# power_supply_and_battery_management.net
KiCad netlist of a schematic drawn in Altium Designer
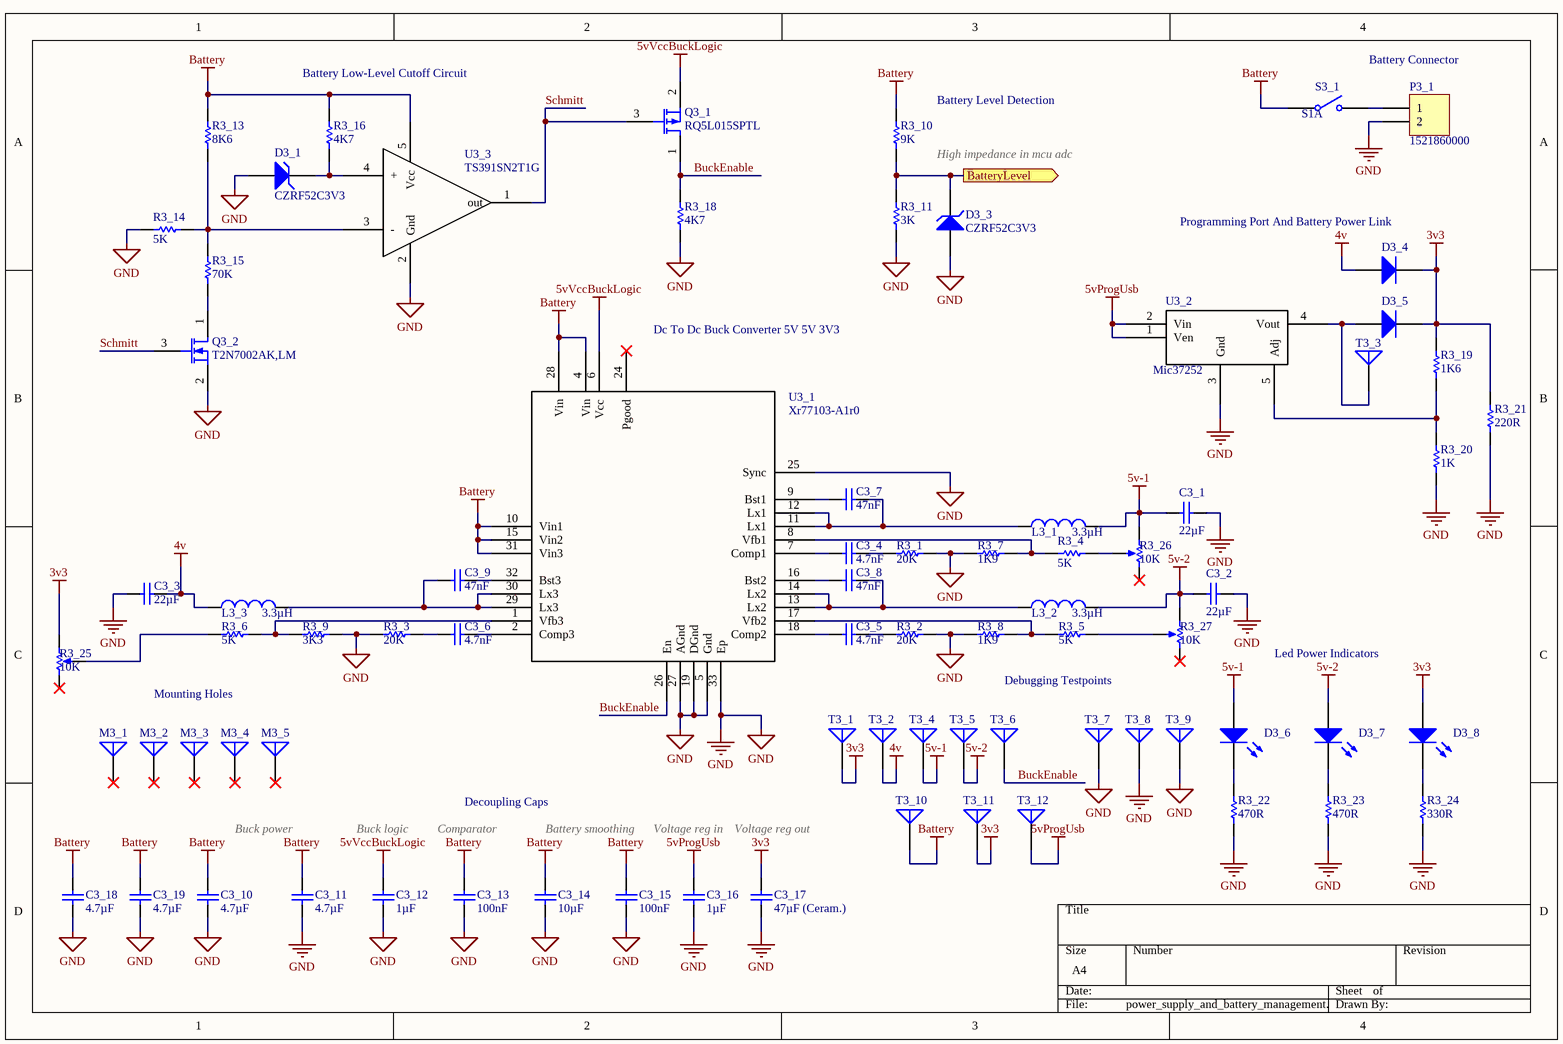
[diagram p0: power_supply_and_battery_management.schdoc]

(export (version "E")
  (design (tool "Eeschema 10.0.6"))
  (components
    (comp (ref "C3_1")
      (value "22µF")
      (footprint "C1206")
      (description "Capacitor")
      (fields (field (name "Comment") "CL31A226KOHNNNE") (field (name "PUBLISHER") "Altium Limited"))
      (libsource (lib "Miscellaneous Devices") (part "Cap"))
    )
    (comp (ref "C3_2")
      (value "22µF")
      (footprint "C1206")
      (description "Capacitor")
      (fields (field (name "Comment") "CL31A226KOHNNNE") (field (name "PUBLISHER") "Altium Limited"))
      (libsource (lib "Miscellaneous Devices") (part "Cap"))
    )
    (comp (ref "C3_3")
      (value "22µF")
      (footprint "C1206")
      (description "Capacitor")
      (fields (field (name "Comment") "CL31A226KOHNNNE") (field (name "PUBLISHER") "Altium Limited"))
      (libsource (lib "Miscellaneous Devices") (part "Cap"))
    )
    (comp (ref "C3_4")
      (value "4.7nF")
      (footprint "C1206")
      (description "Capacitor")
      (fields (field (name "Comment") "CML1206X7R472KT50V") (field (name "PUBLISHER") "Altium Limited"))
      (libsource (lib "Miscellaneous Devices") (part "Cap"))
    )
    (comp (ref "C3_5")
      (value "4.7nF")
      (footprint "C1206")
      (description "Capacitor")
      (fields (field (name "Comment") "CML1206X7R472KT50V") (field (name "PUBLISHER") "Altium Limited"))
      (libsource (lib "Miscellaneous Devices") (part "Cap"))
    )
    (comp (ref "C3_6")
      (value "4.7nF")
      (footprint "C1206")
      (description "Capacitor")
      (fields (field (name "Comment") "CML1206X7R472KT50V") (field (name "PUBLISHER") "Altium Limited"))
      (libsource (lib "Miscellaneous Devices") (part "Cap"))
    )
    (comp (ref "C3_7")
      (value "47nF")
      (footprint "C1206")
      (description "Capacitor")
      (fields (field (name "Comment") "885012208085") (field (name "PUBLISHER") "Altium Limited"))
      (libsource (lib "Miscellaneous Devices") (part "Cap"))
    )
    (comp (ref "C3_8")
      (value "47nF")
      (footprint "C1206")
      (description "Capacitor")
      (fields (field (name "Comment") "885012208085") (field (name "PUBLISHER") "Altium Limited"))
      (libsource (lib "Miscellaneous Devices") (part "Cap"))
    )
    (comp (ref "C3_9")
      (value "47nF")
      (footprint "C1206")
      (description "Capacitor")
      (fields (field (name "Comment") "885012208085") (field (name "PUBLISHER") "Altium Limited"))
      (libsource (lib "Miscellaneous Devices") (part "Cap"))
    )
    (comp (ref "C3_10")
      (value "4.7µF")
      (footprint "C1206")
      (description "Capacitor")
      (fields (field (name "Comment") "CM316X5R475K25AT") (field (name "PUBLISHER") "Altium Limited"))
      (libsource (lib "Miscellaneous Devices") (part "Cap"))
    )
    (comp (ref "C3_11")
      (value "4.7µF")
      (footprint "C1206")
      (description "Capacitor")
      (fields (field (name "Comment") "CM316X5R475K25AT") (field (name "PUBLISHER") "Altium Limited"))
      (libsource (lib "Miscellaneous Devices") (part "Cap"))
    )
    (comp (ref "C3_12")
      (value "1µF")
      (footprint "C1206")
      (description "Capacitor")
      (fields (field (name "Comment") "885382208005") (field (name "PUBLISHER") "Altium Limited"))
      (libsource (lib "Miscellaneous Devices") (part "Cap"))
    )
    (comp (ref "C3_13")
      (value "100nF")
      (footprint "C1206")
      (description "Capacitor")
      (fields (field (name "Comment") "12063C104MAT2A") (field (name "PUBLISHER") "Altium Limited"))
      (libsource (lib "Miscellaneous Devices") (part "Cap"))
    )
    (comp (ref "C3_14")
      (value "10µF")
      (footprint "C1206")
      (description "Capacitor")
      (fields (field (name "Comment") "EMK316BJ106MLHT") (field (name "PUBLISHER") "Altium Limited"))
      (libsource (lib "Miscellaneous Devices") (part "Cap"))
    )
    (comp (ref "C3_15")
      (value "100nF")
      (footprint "C1206")
      (description "Capacitor")
      (fields (field (name "Comment") "12063C104MAT2A") (field (name "PUBLISHER") "Altium Limited"))
      (libsource (lib "Miscellaneous Devices") (part "Cap"))
    )
    (comp (ref "C3_16")
      (value "1µF")
      (footprint "C1206")
      (description "Capacitor")
      (fields (field (name "Comment") "885382208005") (field (name "PUBLISHER") "Altium Limited"))
      (libsource (lib "Miscellaneous Devices") (part "Cap"))
    )
    (comp (ref "C3_17")
      (value "47µF (Ceram.)")
      (footprint "C1206")
      (description "Capacitor")
      (fields (field (name "Comment") "EMK316BBJ476ML-T") (field (name "PUBLISHER") "Altium Limited"))
      (libsource (lib "Miscellaneous Devices") (part "Cap"))
    )
    (comp (ref "C3_18")
      (value "4.7µF")
      (footprint "C1206")
      (description "Capacitor")
      (fields (field (name "Comment") "CM316X5R475K25AT") (field (name "PUBLISHER") "Altium Limited"))
      (libsource (lib "Miscellaneous Devices") (part "Cap"))
    )
    (comp (ref "C3_19")
      (value "4.7µF")
      (footprint "C1206")
      (description "Capacitor")
      (fields (field (name "Comment") "CM316X5R475K25AT") (field (name "PUBLISHER") "Altium Limited"))
      (libsource (lib "Miscellaneous Devices") (part "Cap"))
    )
    (comp (ref "D3_1")
      (value "CZRF52C3V3")
      (footprint "C1206-POLARIZED")
      (description "Zener Diode")
      (fields (field (name "PUBLISHER") "Altium Limited"))
      (libsource (lib "Miscellaneous Devices") (part "D Zener"))
    )
    (comp (ref "D3_3")
      (value "CZRF52C3V3")
      (footprint "C1206-POLARIZED")
      (description "Zener Diode")
      (fields (field (name "PUBLISHER") "Altium Limited"))
      (libsource (lib "Miscellaneous Devices") (part "D Zener"))
    )
    (comp (ref "D3_4")
      (value "ACDBN160-HF")
      (footprint "C1206-POLARIZED")
      (description "Default Diode")
      (fields (field (name "PUBLISHER") "Altium Limited"))
      (libsource (lib "Miscellaneous Devices") (part "Diode"))
    )
    (comp (ref "D3_5")
      (value "ACDBN160-HF")
      (footprint "C1206-POLARIZED")
      (description "Default Diode")
      (fields (field (name "PUBLISHER") "Altium Limited"))
      (libsource (lib "Miscellaneous Devices") (part "Diode"))
    )
    (comp (ref "D3_6")
      (value "APT3216SGC")
      (footprint "C1206-POLARIZED")
      (description "Typical INFRARED GaAs LED")
      (fields (field (name "PUBLISHER") "Altium Limited"))
      (libsource (lib "Miscellaneous Devices") (part "LED0"))
    )
    (comp (ref "D3_7")
      (value "APT3216SGC")
      (footprint "C1206-POLARIZED")
      (description "Typical INFRARED GaAs LED")
      (fields (field (name "PUBLISHER") "Altium Limited"))
      (libsource (lib "Miscellaneous Devices") (part "LED0"))
    )
    (comp (ref "D3_8")
      (value "APT3216SGC")
      (footprint "C1206-POLARIZED")
      (description "Typical INFRARED GaAs LED")
      (fields (field (name "PUBLISHER") "Altium Limited"))
      (libsource (lib "Miscellaneous Devices") (part "LED0"))
    )
    (comp (ref "L3_1")
      (value "3.3µH")
      (footprint "mpxv1D0830")
      (description "Inductor")
      (fields (field (name "Comment") "MPXV1D0830L3R3") (field (name "PUBLISHER") "Altium Limited"))
      (libsource (lib "Miscellaneous Devices") (part "Inductor"))
    )
    (comp (ref "L3_2")
      (value "3.3µH")
      (footprint "mpxv1D0830")
      (description "Inductor")
      (fields (field (name "Comment") "MPXV1D0830L3R3") (field (name "PUBLISHER") "Altium Limited"))
      (libsource (lib "Miscellaneous Devices") (part "Inductor"))
    )
    (comp (ref "L3_3")
      (value "3.3µH")
      (footprint "mpxv1D0830")
      (description "Inductor")
      (fields (field (name "Comment") "MPXV1D0830L3R3") (field (name "PUBLISHER") "Altium Limited"))
      (libsource (lib "Miscellaneous Devices") (part "Inductor"))
    )
    (comp (ref "M3_1")
      (value "Mounting Hole")
      (footprint "MOUNTING-HOLE-M3")
      (description "Generic Antenna")
      (fields (field (name "PUBLISHER") "Altium Limited"))
      (libsource (lib "Miscellaneous Devices") (part "Antenna"))
    )
    (comp (ref "M3_2")
      (value "Mounting Hole")
      (footprint "MOUNTING-HOLE-M3")
      (description "Generic Antenna")
      (fields (field (name "PUBLISHER") "Altium Limited"))
      (libsource (lib "Miscellaneous Devices") (part "Antenna"))
    )
    (comp (ref "M3_3")
      (value "Mounting Hole")
      (footprint "MOUNTING-HOLE-M3")
      (description "Generic Antenna")
      (fields (field (name "PUBLISHER") "Altium Limited"))
      (libsource (lib "Miscellaneous Devices") (part "Antenna"))
    )
    (comp (ref "M3_4")
      (value "Mounting Hole")
      (footprint "MOUNTING-HOLE-M3")
      (description "Generic Antenna")
      (fields (field (name "PUBLISHER") "Altium Limited"))
      (libsource (lib "Miscellaneous Devices") (part "Antenna"))
    )
    (comp (ref "M3_5")
      (value "Mounting Hole")
      (footprint "MOUNTING-HOLE-M3")
      (description "Generic Antenna")
      (fields (field (name "PUBLISHER") "Altium Limited"))
      (libsource (lib "Miscellaneous Devices") (part "Antenna"))
    )
    (comp (ref "P3_1")
      (value "1521860000")
      (footprint "HDR1X2-508-POLARIZED")
      (description "Header, 2-Pin")
      (fields (field (name "PUBLISHER") "Altium Limited"))
      (libsource (lib "Miscellaneous Connectors") (part "Header 2"))
    )
    (comp (ref "Q3_1")
      (value "RQ5L015SPTL")
      (footprint "SOT23_L")
      (description "P-Channel MOSFET")
      (fields (field (name "PUBLISHER") "Altium Limited"))
      (libsource (lib "Miscellaneous Devices") (part "MOSFET-P"))
    )
    (comp (ref "Q3_2")
      (value "T2N7002AK,LM")
      (footprint "SOT23_L")
      (description "N-Channel MOSFET")
      (fields (field (name "PUBLISHER") "Altium Limited"))
      (libsource (lib "Miscellaneous Devices") (part "MOSFET-N"))
    )
    (comp (ref "R3_1")
      (value "20K")
      (footprint "C1206")
      (description "Resistor")
      (fields (field (name "Comment") "Res1") (field (name "PUBLISHER") "Altium Limited"))
      (libsource (lib "Miscellaneous Devices") (part "Res1"))
    )
    (comp (ref "R3_2")
      (value "20K")
      (footprint "C1206")
      (description "Resistor")
      (fields (field (name "Comment") "Res1") (field (name "PUBLISHER") "Altium Limited"))
      (libsource (lib "Miscellaneous Devices") (part "Res1"))
    )
    (comp (ref "R3_3")
      (value "20K")
      (footprint "C1206")
      (description "Resistor")
      (fields (field (name "Comment") "Res1") (field (name "PUBLISHER") "Altium Limited"))
      (libsource (lib "Miscellaneous Devices") (part "Res1"))
    )
    (comp (ref "R3_4")
      (value "5K")
      (footprint "C1206")
      (description "Resistor")
      (fields (field (name "Comment") "Res1") (field (name "PUBLISHER") "Altium Limited"))
      (libsource (lib "Miscellaneous Devices") (part "Res1"))
    )
    (comp (ref "R3_5")
      (value "5K")
      (footprint "C1206")
      (description "Resistor")
      (fields (field (name "Comment") "Res1") (field (name "PUBLISHER") "Altium Limited"))
      (libsource (lib "Miscellaneous Devices") (part "Res1"))
    )
    (comp (ref "R3_6")
      (value "5K")
      (footprint "C1206")
      (description "Resistor")
      (fields (field (name "Comment") "Res1") (field (name "PUBLISHER") "Altium Limited"))
      (libsource (lib "Miscellaneous Devices") (part "Res1"))
    )
    (comp (ref "R3_7")
      (value "1K9")
      (footprint "C1206")
      (description "Resistor")
      (fields (field (name "Comment") "Res1") (field (name "PUBLISHER") "Altium Limited"))
      (libsource (lib "Miscellaneous Devices") (part "Res1"))
    )
    (comp (ref "R3_8")
      (value "1K9")
      (footprint "C1206")
      (description "Resistor")
      (fields (field (name "Comment") "Res1") (field (name "PUBLISHER") "Altium Limited"))
      (libsource (lib "Miscellaneous Devices") (part "Res1"))
    )
    (comp (ref "R3_9")
      (value "3K3")
      (footprint "C1206")
      (description "Resistor")
      (fields (field (name "Comment") "Res1") (field (name "PUBLISHER") "Altium Limited"))
      (libsource (lib "Miscellaneous Devices") (part "Res1"))
    )
    (comp (ref "R3_10")
      (value "9K")
      (footprint "C1206")
      (description "Resistor")
      (fields (field (name "Comment") "Res1") (field (name "PUBLISHER") "Altium Limited"))
      (libsource (lib "Miscellaneous Devices") (part "Res1"))
    )
    (comp (ref "R3_11")
      (value "3K")
      (footprint "C1206")
      (description "Resistor")
      (fields (field (name "Comment") "Res1") (field (name "PUBLISHER") "Altium Limited"))
      (libsource (lib "Miscellaneous Devices") (part "Res1"))
    )
    (comp (ref "R3_13")
      (value "8K6")
      (footprint "C1206")
      (description "Resistor")
      (fields (field (name "Comment") "Res1") (field (name "PUBLISHER") "Altium Limited"))
      (libsource (lib "Miscellaneous Devices") (part "Res1"))
    )
    (comp (ref "R3_14")
      (value "5K")
      (footprint "C1206")
      (description "Resistor")
      (fields (field (name "Comment") "Res1") (field (name "PUBLISHER") "Altium Limited"))
      (libsource (lib "Miscellaneous Devices") (part "Res1"))
    )
    (comp (ref "R3_15")
      (value "70K")
      (footprint "C1206")
      (description "Resistor")
      (fields (field (name "Comment") "Res1") (field (name "PUBLISHER") "Altium Limited"))
      (libsource (lib "Miscellaneous Devices") (part "Res1"))
    )
    (comp (ref "R3_16")
      (value "4K7")
      (footprint "C1206")
      (description "Resistor")
      (fields (field (name "Comment") "Res1") (field (name "PUBLISHER") "Altium Limited"))
      (libsource (lib "Miscellaneous Devices") (part "Res1"))
    )
    (comp (ref "R3_18")
      (value "4K7")
      (footprint "C1206")
      (description "Resistor")
      (fields (field (name "Comment") "Res1") (field (name "PUBLISHER") "Altium Limited"))
      (libsource (lib "Miscellaneous Devices") (part "Res1"))
    )
    (comp (ref "R3_19")
      (value "1K6")
      (footprint "C1206")
      (description "Resistor")
      (fields (field (name "Comment") "Res1") (field (name "PUBLISHER") "Altium Limited"))
      (libsource (lib "Miscellaneous Devices") (part "Res1"))
    )
    (comp (ref "R3_20")
      (value "1K")
      (footprint "C1206")
      (description "Resistor")
      (fields (field (name "Comment") "Res1") (field (name "PUBLISHER") "Altium Limited"))
      (libsource (lib "Miscellaneous Devices") (part "Res1"))
    )
    (comp (ref "R3_21")
      (value "220R")
      (footprint "C1206")
      (description "Resistor")
      (fields (field (name "Comment") "Res1") (field (name "PUBLISHER") "Altium Limited"))
      (libsource (lib "Miscellaneous Devices") (part "Res1"))
    )
    (comp (ref "R3_22")
      (value "470R")
      (footprint "C1206")
      (description "Resistor")
      (fields (field (name "Comment") "Res1") (field (name "PUBLISHER") "Altium Limited"))
      (libsource (lib "Miscellaneous Devices") (part "Res1"))
    )
    (comp (ref "R3_23")
      (value "470R")
      (footprint "C1206")
      (description "Resistor")
      (fields (field (name "Comment") "Res1") (field (name "PUBLISHER") "Altium Limited"))
      (libsource (lib "Miscellaneous Devices") (part "Res1"))
    )
    (comp (ref "R3_24")
      (value "330R")
      (footprint "C1206")
      (description "Resistor")
      (fields (field (name "Comment") "Res1") (field (name "PUBLISHER") "Altium Limited"))
      (libsource (lib "Miscellaneous Devices") (part "Res1"))
    )
    (comp (ref "R3_25")
      (value "10K")
      (footprint "ST-4ETA103")
      (description "Potentiometer")
      (fields (field (name "Comment") "ST4ETA103") (field (name "PUBLISHER") "Altium Limited"))
      (libsource (lib "") (part "RPot_1"))
    )
    (comp (ref "R3_26")
      (value "10K")
      (footprint "ST-4ETA103")
      (description "Potentiometer")
      (fields (field (name "Comment") "ST4ETA103") (field (name "PUBLISHER") "Altium Limited"))
      (libsource (lib "Miscellaneous Devices") (part "RPot"))
    )
    (comp (ref "R3_27")
      (value "10K")
      (footprint "ST-4ETA103")
      (description "Potentiometer")
      (fields (field (name "Comment") "ST4ETA103") (field (name "PUBLISHER") "Altium Limited"))
      (libsource (lib "Miscellaneous Devices") (part "RPot"))
    )
    (comp (ref "S3_1")
      (value "S1A")
      (footprint "SW2-THR")
      (description "Single-Pole, Single-Throw Switch")
      (fields (field (name "PUBLISHER") "Altium Limited"))
      (libsource (lib "Miscellaneous Devices") (part "SW-SPST"))
    )
    (comp (ref "T3_1")
      (value "Mounting Hole")
      (footprint "TESTPOINT")
      (description "Generic Antenna")
      (fields (field (name "PUBLISHER") "Altium Limited"))
      (libsource (lib "Miscellaneous Devices") (part "Antenna"))
    )
    (comp (ref "T3_2")
      (value "Mounting Hole")
      (footprint "TESTPOINT")
      (description "Generic Antenna")
      (fields (field (name "PUBLISHER") "Altium Limited"))
      (libsource (lib "Miscellaneous Devices") (part "Antenna"))
    )
    (comp (ref "T3_3")
      (value "Mounting Hole")
      (footprint "TESTPOINT")
      (description "Generic Antenna")
      (fields (field (name "PUBLISHER") "Altium Limited"))
      (libsource (lib "Miscellaneous Devices") (part "Antenna"))
    )
    (comp (ref "T3_4")
      (value "Mounting Hole")
      (footprint "TESTPOINT")
      (description "Generic Antenna")
      (fields (field (name "PUBLISHER") "Altium Limited"))
      (libsource (lib "Miscellaneous Devices") (part "Antenna"))
    )
    (comp (ref "T3_5")
      (value "Mounting Hole")
      (footprint "TESTPOINT")
      (description "Generic Antenna")
      (fields (field (name "PUBLISHER") "Altium Limited"))
      (libsource (lib "Miscellaneous Devices") (part "Antenna"))
    )
    (comp (ref "T3_6")
      (value "Mounting Hole")
      (footprint "TESTPOINT")
      (description "Generic Antenna")
      (fields (field (name "PUBLISHER") "Altium Limited"))
      (libsource (lib "Miscellaneous Devices") (part "Antenna"))
    )
    (comp (ref "T3_7")
      (value "Mounting Hole")
      (footprint "TESTPOINT")
      (description "Generic Antenna")
      (fields (field (name "PUBLISHER") "Altium Limited"))
      (libsource (lib "Miscellaneous Devices") (part "Antenna"))
    )
    (comp (ref "T3_8")
      (value "Mounting Hole")
      (footprint "TESTPOINT")
      (description "Generic Antenna")
      (fields (field (name "PUBLISHER") "Altium Limited"))
      (libsource (lib "Miscellaneous Devices") (part "Antenna"))
    )
    (comp (ref "T3_9")
      (value "Mounting Hole")
      (footprint "TESTPOINT")
      (description "Generic Antenna")
      (fields (field (name "PUBLISHER") "Altium Limited"))
      (libsource (lib "Miscellaneous Devices") (part "Antenna"))
    )
    (comp (ref "T3_10")
      (value "Mounting Hole")
      (footprint "TESTPOINT")
      (description "Generic Antenna")
      (fields (field (name "PUBLISHER") "Altium Limited"))
      (libsource (lib "Miscellaneous Devices") (part "Antenna"))
    )
    (comp (ref "T3_11")
      (value "Mounting Hole")
      (footprint "TESTPOINT")
      (description "Generic Antenna")
      (fields (field (name "PUBLISHER") "Altium Limited"))
      (libsource (lib "Miscellaneous Devices") (part "Antenna"))
    )
    (comp (ref "T3_12")
      (value "Mounting Hole")
      (footprint "TESTPOINT")
      (description "Generic Antenna")
      (fields (field (name "PUBLISHER") "Altium Limited"))
      (libsource (lib "Miscellaneous Devices") (part "Antenna"))
    )
    (comp (ref "U3_1")
      (value "Xr77103-A1r0")
      (footprint "32-TQFN (4x4)")
      (description "Dc to dc step down converter")
      (libsource (lib "projet 6e session") (part "Xr77103-A1r0"))
    )
    (comp (ref "U3_2")
      (value "Mic37252")
      (footprint "TO-263 (5)")
      (libsource (lib "projet 6e session") (part "Mic37252"))
    )
    (comp (ref "U3_3")
      (value "TS391SN2T1G")
      (footprint "TSOP5(6)")
      (libsource (lib "projet 6e session") (part "Op Amp"))
    )
  )
  (nets
    (net (code "1") (name "/BatteryLevel") (class "Default")
      (node (ref "D3_3") (pin "2") (pinfunction "K_2") (pintype "passive"))
      (node (ref "R3_10") (pin "1") (pinfunction "1_1") (pintype "passive"))
      (node (ref "R3_11") (pin "2") (pinfunction "2_2") (pintype "passive"))
    )
    (net (code "2") (name "/BuckEnable") (class "Default")
      (node (ref "Q3_1") (pin "1") (pinfunction "D_1") (pintype "passive"))
      (node (ref "R3_18") (pin "2") (pinfunction "2_2") (pintype "passive"))
      (node (ref "T3_6") (pin "1") (pinfunction "A_1") (pintype "passive"))
      (node (ref "U3_1") (pin "26") (pinfunction "En_26") (pintype "passive"))
    )
    (net (code "3") (name "/Schmitt") (class "Default")
      (node (ref "Q3_1") (pin "3") (pinfunction "G_3") (pintype "passive"))
      (node (ref "Q3_2") (pin "3") (pinfunction "G_3") (pintype "passive"))
      (node (ref "U3_3") (pin "1") (pinfunction "out_1") (pintype "passive"))
    )
    (net (code "4") (name "3v3") (class "Default")
      (node (ref "C3_17") (pin "2") (pinfunction "2_2") (pintype "passive"))
      (node (ref "D3_4") (pin "2") (pinfunction "K_2") (pintype "passive"))
      (node (ref "D3_5") (pin "2") (pinfunction "K_2") (pintype "passive"))
      (node (ref "D3_8") (pin "1") (pinfunction "A_1") (pintype "passive"))
      (node (ref "R3_19") (pin "1") (pinfunction "1_1") (pintype "passive"))
      (node (ref "R3_21") (pin "1") (pinfunction "1_1") (pintype "passive"))
      (node (ref "R3_25") (pin "1") (pinfunction "BOT_1") (pintype "passive"))
      (node (ref "T3_1") (pin "1") (pinfunction "A_1") (pintype "passive"))
      (node (ref "T3_11") (pin "1") (pinfunction "A_1") (pintype "passive"))
    )
    (net (code "5") (name "4v") (class "Default")
      (node (ref "C3_3") (pin "2") (pinfunction "2_2") (pintype "passive"))
      (node (ref "D3_4") (pin "1") (pinfunction "A_1") (pintype "passive"))
      (node (ref "L3_3") (pin "1") (pinfunction "1_1") (pintype "passive"))
      (node (ref "T3_2") (pin "1") (pinfunction "A_1") (pintype "passive"))
    )
    (net (code "6") (name "5v-1") (class "Default")
      (node (ref "C3_1") (pin "2") (pinfunction "2_2") (pintype "passive"))
      (node (ref "D3_6") (pin "1") (pinfunction "A_1") (pintype "passive"))
      (node (ref "L3_1") (pin "2") (pinfunction "2_2") (pintype "passive"))
      (node (ref "R3_26") (pin "1") (pinfunction "TOP_1") (pintype "passive"))
      (node (ref "T3_4") (pin "1") (pinfunction "A_1") (pintype "passive"))
    )
    (net (code "7") (name "5v-2") (class "Default")
      (node (ref "C3_2") (pin "2") (pinfunction "2_2") (pintype "passive"))
      (node (ref "D3_7") (pin "1") (pinfunction "A_1") (pintype "passive"))
      (node (ref "L3_2") (pin "2") (pinfunction "2_2") (pintype "passive"))
      (node (ref "R3_27") (pin "1") (pinfunction "TOP_1") (pintype "passive"))
      (node (ref "T3_5") (pin "1") (pinfunction "A_1") (pintype "passive"))
    )
    (net (code "8") (name "5vProgUsb") (class "Default")
      (node (ref "C3_16") (pin "2") (pinfunction "2_2") (pintype "passive"))
      (node (ref "T3_12") (pin "1") (pinfunction "A_1") (pintype "passive"))
      (node (ref "U3_2") (pin "1") (pinfunction "Ven_1") (pintype "passive"))
      (node (ref "U3_2") (pin "2") (pinfunction "Vin_2") (pintype "passive"))
    )
    (net (code "9") (name "5vVccBuckLogic") (class "Default")
      (node (ref "C3_12") (pin "2") (pinfunction "2_2") (pintype "passive"))
      (node (ref "Q3_1") (pin "2") (pinfunction "S_2") (pintype "passive"))
      (node (ref "U3_1") (pin "6") (pinfunction "Vcc_6") (pintype "passive"))
    )
    (net (code "10") (name "Battery") (class "Default")
      (node (ref "C3_10") (pin "2") (pinfunction "2_2") (pintype "passive"))
      (node (ref "C3_11") (pin "2") (pinfunction "2_2") (pintype "passive"))
      (node (ref "C3_13") (pin "2") (pinfunction "2_2") (pintype "passive"))
      (node (ref "C3_14") (pin "2") (pinfunction "2_2") (pintype "passive"))
      (node (ref "C3_15") (pin "2") (pinfunction "2_2") (pintype "passive"))
      (node (ref "C3_18") (pin "2") (pinfunction "2_2") (pintype "passive"))
      (node (ref "C3_19") (pin "2") (pinfunction "2_2") (pintype "passive"))
      (node (ref "R3_10") (pin "2") (pinfunction "2_2") (pintype "passive"))
      (node (ref "R3_13") (pin "2") (pinfunction "2_2") (pintype "passive"))
      (node (ref "R3_16") (pin "2") (pinfunction "2_2") (pintype "passive"))
      (node (ref "S3_1") (pin "1") (pinfunction "COMMON_1") (pintype "passive"))
      (node (ref "T3_10") (pin "1") (pinfunction "A_1") (pintype "passive"))
      (node (ref "U3_1") (pin "10") (pinfunction "Vin1_10") (pintype "passive"))
      (node (ref "U3_1") (pin "15") (pinfunction "Vin2_15") (pintype "passive"))
      (node (ref "U3_1") (pin "28") (pinfunction "Vin_28") (pintype "passive"))
      (node (ref "U3_1") (pin "31") (pinfunction "Vin3_31") (pintype "passive"))
      (node (ref "U3_1") (pin "4") (pinfunction "Vin_4") (pintype "passive"))
      (node (ref "U3_3") (pin "5") (pinfunction "Vcc_5") (pintype "passive"))
    )
    (net (code "11") (name "GND") (class "Default")
      (node (ref "C3_1") (pin "1") (pinfunction "1_1") (pintype "passive"))
      (node (ref "C3_10") (pin "1") (pinfunction "1_1") (pintype "passive"))
      (node (ref "C3_11") (pin "1") (pinfunction "1_1") (pintype "passive"))
      (node (ref "C3_12") (pin "1") (pinfunction "1_1") (pintype "passive"))
      (node (ref "C3_13") (pin "1") (pinfunction "1_1") (pintype "passive"))
      (node (ref "C3_14") (pin "1") (pinfunction "1_1") (pintype "passive"))
      (node (ref "C3_15") (pin "1") (pinfunction "1_1") (pintype "passive"))
      (node (ref "C3_16") (pin "1") (pinfunction "1_1") (pintype "passive"))
      (node (ref "C3_17") (pin "1") (pinfunction "1_1") (pintype "passive"))
      (node (ref "C3_18") (pin "1") (pinfunction "1_1") (pintype "passive"))
      (node (ref "C3_19") (pin "1") (pinfunction "1_1") (pintype "passive"))
      (node (ref "C3_2") (pin "1") (pinfunction "1_1") (pintype "passive"))
      (node (ref "C3_3") (pin "1") (pinfunction "1_1") (pintype "passive"))
      (node (ref "D3_1") (pin "1") (pinfunction "A_1") (pintype "passive"))
      (node (ref "D3_3") (pin "1") (pinfunction "A_1") (pintype "passive"))
      (node (ref "P3_1") (pin "2") (pinfunction "2_2") (pintype "passive"))
      (node (ref "Q3_2") (pin "2") (pinfunction "S_2") (pintype "passive"))
      (node (ref "R3_1") (pin "2") (pinfunction "2_2") (pintype "passive"))
      (node (ref "R3_11") (pin "1") (pinfunction "1_1") (pintype "passive"))
      (node (ref "R3_14") (pin "1") (pinfunction "1_1") (pintype "passive"))
      (node (ref "R3_18") (pin "1") (pinfunction "1_1") (pintype "passive"))
      (node (ref "R3_2") (pin "2") (pinfunction "2_2") (pintype "passive"))
      (node (ref "R3_20") (pin "2") (pinfunction "2_2") (pintype "passive"))
      (node (ref "R3_21") (pin "2") (pinfunction "2_2") (pintype "passive"))
      (node (ref "R3_22") (pin "2") (pinfunction "2_2") (pintype "passive"))
      (node (ref "R3_23") (pin "2") (pinfunction "2_2") (pintype "passive"))
      (node (ref "R3_24") (pin "2") (pinfunction "2_2") (pintype "passive"))
      (node (ref "R3_3") (pin "1") (pinfunction "1_1") (pintype "passive"))
      (node (ref "R3_7") (pin "1") (pinfunction "1_1") (pintype "passive"))
      (node (ref "R3_8") (pin "1") (pinfunction "1_1") (pintype "passive"))
      (node (ref "R3_9") (pin "2") (pinfunction "2_2") (pintype "passive"))
      (node (ref "T3_7") (pin "1") (pinfunction "A_1") (pintype "passive"))
      (node (ref "T3_8") (pin "1") (pinfunction "A_1") (pintype "passive"))
      (node (ref "T3_9") (pin "1") (pinfunction "A_1") (pintype "passive"))
      (node (ref "U3_1") (pin "19") (pinfunction "DGnd_19") (pintype "passive"))
      (node (ref "U3_1") (pin "25") (pinfunction "Sync_25") (pintype "passive"))
      (node (ref "U3_1") (pin "27") (pinfunction "AGnd_27") (pintype "passive"))
      (node (ref "U3_1") (pin "33") (pinfunction "Ep_33") (pintype "passive"))
      (node (ref "U3_1") (pin "5") (pinfunction "Gnd_5") (pintype "passive"))
      (node (ref "U3_2") (pin "3") (pinfunction "Gnd_3") (pintype "passive"))
      (node (ref "U3_3") (pin "2") (pinfunction "Gnd_2") (pintype "passive"))
    )
    (net (code "12") (name "Net-(C3_4-Pad2)") (class "Default")
      (node (ref "C3_4") (pin "2") (pinfunction "2_2") (pintype "passive"))
      (node (ref "R3_1") (pin "1") (pinfunction "1_1") (pintype "passive"))
    )
    (net (code "13") (name "Net-(C3_5-Pad2)") (class "Default")
      (node (ref "C3_5") (pin "2") (pinfunction "2_2") (pintype "passive"))
      (node (ref "R3_2") (pin "1") (pinfunction "1_1") (pintype "passive"))
    )
    (net (code "14") (name "Net-(C3_6-Pad1)") (class "Default")
      (node (ref "C3_6") (pin "1") (pinfunction "1_1") (pintype "passive"))
      (node (ref "R3_3") (pin "2") (pinfunction "2_2") (pintype "passive"))
    )
    (net (code "15") (name "Net-(C3_7-Pad2)") (class "Default")
      (node (ref "C3_7") (pin "2") (pinfunction "2_2") (pintype "passive"))
      (node (ref "L3_1") (pin "1") (pinfunction "1_1") (pintype "passive"))
      (node (ref "U3_1") (pin "11") (pinfunction "Lx1_11") (pintype "passive"))
      (node (ref "U3_1") (pin "12") (pinfunction "Lx1_12") (pintype "passive"))
    )
    (net (code "16") (name "Net-(C3_8-Pad2)") (class "Default")
      (node (ref "C3_8") (pin "2") (pinfunction "2_2") (pintype "passive"))
      (node (ref "L3_2") (pin "1") (pinfunction "1_1") (pintype "passive"))
      (node (ref "U3_1") (pin "13") (pinfunction "Lx2_13") (pintype "passive"))
      (node (ref "U3_1") (pin "14") (pinfunction "Lx2_14") (pintype "passive"))
    )
    (net (code "17") (name "Net-(C3_9-Pad1)") (class "Default")
      (node (ref "C3_9") (pin "1") (pinfunction "1_1") (pintype "passive"))
      (node (ref "L3_3") (pin "2") (pinfunction "2_2") (pintype "passive"))
      (node (ref "U3_1") (pin "29") (pinfunction "Lx3_29") (pintype "passive"))
      (node (ref "U3_1") (pin "30") (pinfunction "Lx3_30") (pintype "passive"))
    )
    (net (code "18") (name "Net-(D3_1-K)") (class "Default")
      (node (ref "D3_1") (pin "2") (pinfunction "K_2") (pintype "passive"))
      (node (ref "R3_16") (pin "1") (pinfunction "1_1") (pintype "passive"))
      (node (ref "U3_3") (pin "4") (pinfunction "+_4") (pintype "passive"))
    )
    (net (code "19") (name "Net-(D3_5-A)") (class "Default")
      (node (ref "D3_5") (pin "1") (pinfunction "A_1") (pintype "passive"))
      (node (ref "T3_3") (pin "1") (pinfunction "A_1") (pintype "passive"))
      (node (ref "U3_2") (pin "4") (pinfunction "Vout_4") (pintype "passive"))
    )
    (net (code "20") (name "Net-(D3_6-K)") (class "Default")
      (node (ref "D3_6") (pin "2") (pinfunction "K_2") (pintype "passive"))
      (node (ref "R3_22") (pin "1") (pinfunction "1_1") (pintype "passive"))
    )
    (net (code "21") (name "Net-(D3_7-K)") (class "Default")
      (node (ref "D3_7") (pin "2") (pinfunction "K_2") (pintype "passive"))
      (node (ref "R3_23") (pin "1") (pinfunction "1_1") (pintype "passive"))
    )
    (net (code "22") (name "Net-(D3_8-K)") (class "Default")
      (node (ref "D3_8") (pin "2") (pinfunction "K_2") (pintype "passive"))
      (node (ref "R3_24") (pin "1") (pinfunction "1_1") (pintype "passive"))
    )
    (net (code "23") (name "Net-(Q3_2-D)") (class "Default")
      (node (ref "Q3_2") (pin "1") (pinfunction "D_1") (pintype "passive"))
      (node (ref "R3_15") (pin "1") (pinfunction "1_1") (pintype "passive"))
    )
    (net (code "24") (name "Net-(R3_25-TAP)") (class "Default")
      (node (ref "R3_25") (pin "3") (pinfunction "TAP_3") (pintype "passive"))
      (node (ref "R3_6") (pin "1") (pinfunction "1_1") (pintype "passive"))
    )
    (net (code "25") (name "Net-(R3_26-TAP)") (class "Default")
      (node (ref "R3_26") (pin "3") (pinfunction "TAP_3") (pintype "passive"))
      (node (ref "R3_4") (pin "2") (pinfunction "2_2") (pintype "passive"))
    )
    (net (code "26") (name "Net-(R3_27-TAP)") (class "Default")
      (node (ref "R3_27") (pin "3") (pinfunction "TAP_3") (pintype "passive"))
      (node (ref "R3_5") (pin "2") (pinfunction "2_2") (pintype "passive"))
    )
    (net (code "27") (name "Net-(S3_1-NO)") (class "Default")
      (node (ref "P3_1") (pin "1") (pinfunction "1_1") (pintype "passive"))
      (node (ref "S3_1") (pin "2") (pinfunction "NO_2") (pintype "passive"))
    )
    (net (code "28") (name "Net-(U3_1-Bst1)") (class "Default")
      (node (ref "C3_7") (pin "1") (pinfunction "1_1") (pintype "passive"))
      (node (ref "U3_1") (pin "9") (pinfunction "Bst1_9") (pintype "passive"))
    )
    (net (code "29") (name "Net-(U3_1-Bst2)") (class "Default")
      (node (ref "C3_8") (pin "1") (pinfunction "1_1") (pintype "passive"))
      (node (ref "U3_1") (pin "16") (pinfunction "Bst2_16") (pintype "passive"))
    )
    (net (code "30") (name "Net-(U3_1-Bst3)") (class "Default")
      (node (ref "C3_9") (pin "2") (pinfunction "2_2") (pintype "passive"))
      (node (ref "U3_1") (pin "32") (pinfunction "Bst3_32") (pintype "passive"))
    )
    (net (code "31") (name "Net-(U3_1-Comp1)") (class "Default")
      (node (ref "C3_4") (pin "1") (pinfunction "1_1") (pintype "passive"))
      (node (ref "U3_1") (pin "7") (pinfunction "Comp1_7") (pintype "passive"))
    )
    (net (code "32") (name "Net-(U3_1-Comp2)") (class "Default")
      (node (ref "C3_5") (pin "1") (pinfunction "1_1") (pintype "passive"))
      (node (ref "U3_1") (pin "18") (pinfunction "Comp2_18") (pintype "passive"))
    )
    (net (code "33") (name "Net-(U3_1-Comp3)") (class "Default")
      (node (ref "C3_6") (pin "2") (pinfunction "2_2") (pintype "passive"))
      (node (ref "U3_1") (pin "2") (pinfunction "Comp3_2") (pintype "passive"))
    )
    (net (code "34") (name "Net-(U3_1-Vfb1)") (class "Default")
      (node (ref "R3_4") (pin "1") (pinfunction "1_1") (pintype "passive"))
      (node (ref "R3_7") (pin "2") (pinfunction "2_2") (pintype "passive"))
      (node (ref "U3_1") (pin "8") (pinfunction "Vfb1_8") (pintype "passive"))
    )
    (net (code "35") (name "Net-(U3_1-Vfb2)") (class "Default")
      (node (ref "R3_5") (pin "1") (pinfunction "1_1") (pintype "passive"))
      (node (ref "R3_8") (pin "2") (pinfunction "2_2") (pintype "passive"))
      (node (ref "U3_1") (pin "17") (pinfunction "Vfb2_17") (pintype "passive"))
    )
    (net (code "36") (name "Net-(U3_1-Vfb3)") (class "Default")
      (node (ref "R3_6") (pin "2") (pinfunction "2_2") (pintype "passive"))
      (node (ref "R3_9") (pin "1") (pinfunction "1_1") (pintype "passive"))
      (node (ref "U3_1") (pin "1") (pinfunction "Vfb3_1") (pintype "passive"))
    )
    (net (code "37") (name "Net-(U3_2-Adj)") (class "Default")
      (node (ref "R3_19") (pin "2") (pinfunction "2_2") (pintype "passive"))
      (node (ref "R3_20") (pin "1") (pinfunction "1_1") (pintype "passive"))
      (node (ref "U3_2") (pin "5") (pinfunction "Adj_5") (pintype "passive"))
    )
    (net (code "38") (name "Net-(U3_3--)") (class "Default")
      (node (ref "R3_13") (pin "1") (pinfunction "1_1") (pintype "passive"))
      (node (ref "R3_14") (pin "2") (pinfunction "2_2") (pintype "passive"))
      (node (ref "R3_15") (pin "2") (pinfunction "2_2") (pintype "passive"))
      (node (ref "U3_3") (pin "3") (pinfunction "-_3") (pintype "passive"))
    )
    (net (code "39") (name "unconnected-(M3_1-A-Pad1)") (class "Default")
      (node (ref "M3_1") (pin "1") (pinfunction "A_1") (pintype "passive+no_connect"))
    )
    (net (code "40") (name "unconnected-(M3_2-A-Pad1)") (class "Default")
      (node (ref "M3_2") (pin "1") (pinfunction "A_1") (pintype "passive+no_connect"))
    )
    (net (code "41") (name "unconnected-(M3_3-A-Pad1)") (class "Default")
      (node (ref "M3_3") (pin "1") (pinfunction "A_1") (pintype "passive+no_connect"))
    )
    (net (code "42") (name "unconnected-(M3_4-A-Pad1)") (class "Default")
      (node (ref "M3_4") (pin "1") (pinfunction "A_1") (pintype "passive+no_connect"))
    )
    (net (code "43") (name "unconnected-(M3_5-A-Pad1)") (class "Default")
      (node (ref "M3_5") (pin "1") (pinfunction "A_1") (pintype "passive+no_connect"))
    )
    (net (code "44") (name "unconnected-(R3_25-TOP-Pad2)") (class "Default")
      (node (ref "R3_25") (pin "2") (pinfunction "TOP_2") (pintype "passive+no_connect"))
    )
    (net (code "45") (name "unconnected-(R3_26-BOT-Pad2)") (class "Default")
      (node (ref "R3_26") (pin "2") (pinfunction "BOT_2") (pintype "passive+no_connect"))
    )
    (net (code "46") (name "unconnected-(R3_27-BOT-Pad2)") (class "Default")
      (node (ref "R3_27") (pin "2") (pinfunction "BOT_2") (pintype "passive+no_connect"))
    )
    (net (code "47") (name "unconnected-(U3_1-Pgood-Pad24)") (class "Default")
      (node (ref "U3_1") (pin "24") (pinfunction "Pgood_24") (pintype "passive+no_connect"))
    )
  )
)
